# board1.net
KiCad netlist of a schematic drawn in Altium Designer
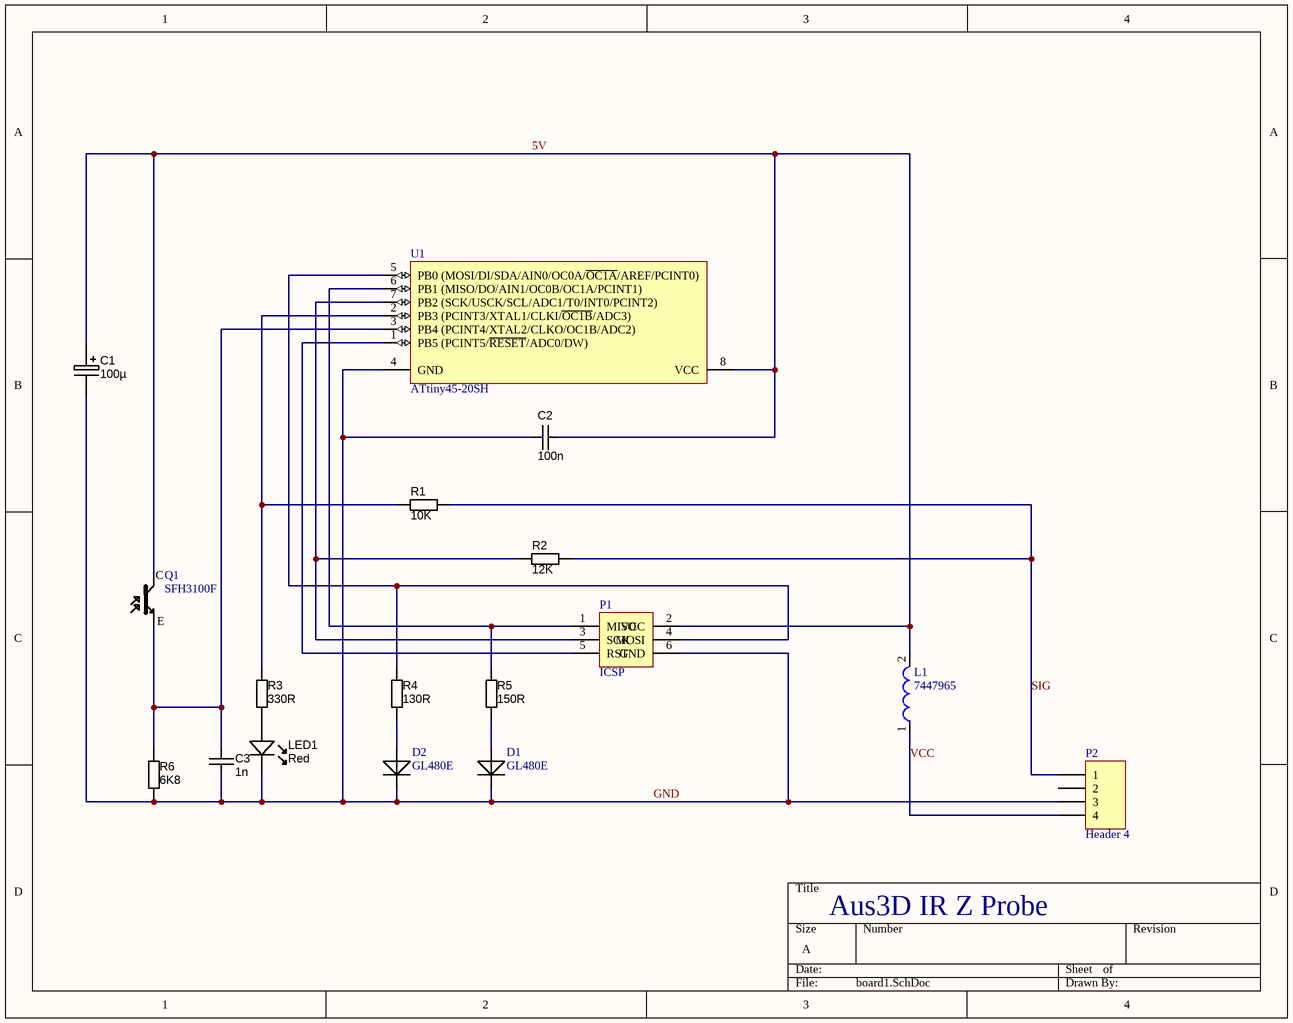
[diagram p0: board1.SchDoc]

(export (version "E")
  (design (tool "Eeschema 10.0.6"))
  (components
    (comp (ref "C1")
      (value "100µ")
      (footprint "6.3-DIA-CAP")
      (description "Capacitor THD Electrolytic 100uF 20% 16V Radial")
      (fields (field (name "TOLERANCE") "±20%") (field (name "MANUFACTURER") "Panasonic - ECG"))
      (libsource (lib "PBL - Capacitors") (part "CAPE_100u_16V_THD"))
    )
    (comp (ref "C2")
      (value "100n")
      (footprint "CAPC1005X55N")
      (description "Capacitor SMD Cer 100nF 10% 16V X5R 0402")
      (fields (field (name "TOLERANCE") "±10%"))
      (libsource (lib "PBL - Capacitors") (part "CAPC_100n_0402_X5R_16V_10%"))
    )
    (comp (ref "C3")
      (value "1n")
      (footprint "CAPC1005X55N")
      (description "Capacitor SMD Cer 1nF 10% 16V X7R 0402")
      (fields (field (name "TOLERANCE") "±10%"))
      (libsource (lib "PBL - Capacitors") (part "CAPC_1n_0402_X7R_16V_10%"))
    )
    (comp (ref "D1")
      (value "GL480E")
      (footprint "LED-2.54spacing")
      (libsource (lib "Schlib1") (part "GL480E"))
    )
    (comp (ref "D2")
      (value "GL480E")
      (footprint "LED-2.54spacing")
      (libsource (lib "Schlib1") (part "GL480E"))
    )
    (comp (ref "L1")
      (value "7447965")
      (footprint "SMD-0603")
      (description "SMD-Multilayer Inductor WE-MI, L = 1.00 µH")
      (libsource (lib "Wuerth Elektronik Filter Inductor") (part "7447965"))
    )
    (comp (ref "LED1")
      (value "Red")
      (footprint "LED-0603-RED")
      (description "LED 0603 SMD Hyper Red 630nm 220mcd 20mA")
      (libsource (lib "PBL - Light Sources") (part "LED_SMD_Red_0603_220mcd"))
    )
    (comp (ref "P1")
      (value "ICSP")
      (footprint "HDR2X3")
      (description "Header, 3-Pin, Dual row")
      (fields (field (name "PUBLISHER") "Altium Limited"))
      (libsource (lib "Miscellaneous Connectors") (part "Header 3X2"))
    )
    (comp (ref "P2")
      (value "Header 4")
      (footprint "JST-4P")
      (description "Header, 4-Pin")
      (fields (field (name "PUBLISHER") "Altium Limited"))
      (libsource (lib "Miscellaneous Connectors") (part "Header 4"))
    )
    (comp (ref "Q1")
      (value "SFH3100F")
      (footprint "SFH3100F-footprint")
      (description "GL480E")
      (libsource (lib "Schlib1") (part "SFH3100F"))
    )
    (comp (ref "R1")
      (value "10K")
      (footprint "RESC1608X55N")
      (description "Resistor SMD chip 2.2k Ohm 0.1W 5% 0603")
      (fields (field (name "TOLERANCE") "±5%") (field (name "Comment") "Thick Film"))
      (libsource (lib "") (part "RES_2K2_0603_5%_1"))
    )
    (comp (ref "R2")
      (value "12K")
      (footprint "RESC1608X55N")
      (description "Resistor SMD chip 2.2k Ohm 0.1W 5% 0603")
      (fields (field (name "TOLERANCE") "±5%") (field (name "Comment") "Thick Film"))
      (libsource (lib "") (part "RES_2K2_0603_5%_1"))
    )
    (comp (ref "R3")
      (value "330R")
      (footprint "RESC1608X55N")
      (description "Resistor SMD chip 330 Ohm 0.1W 5% 0603")
      (fields (field (name "TOLERANCE") "±5%") (field (name "Comment") "Thick Film"))
      (libsource (lib "PBL - Resistors") (part "RES_330R_0603_5%"))
    )
    (comp (ref "R4")
      (value "130R")
      (footprint "RESC1608X55N")
      (description "Resistor SMD chip 2.2k Ohm 0.1W 5% 0603")
      (fields (field (name "TOLERANCE") "±5%") (field (name "Comment") "Thick Film"))
      (libsource (lib "PBL - Resistors") (part "RES_2K2_0603_5%"))
    )
    (comp (ref "R5")
      (value "150R")
      (footprint "RESC1608X55N")
      (description "Resistor SMD chip 2.2k Ohm 0.1W 5% 0603")
      (fields (field (name "TOLERANCE") "±5%") (field (name "Comment") "Thick Film"))
      (libsource (lib "PBL - Resistors") (part "RES_2K2_0603_5%"))
    )
    (comp (ref "R6")
      (value "6K8")
      (footprint "RESC1608X55N")
      (description "Resistor SMD chip 2.2k Ohm 0.1W 5% 0603")
      (fields (field (name "TOLERANCE") "±5%") (field (name "Comment") "Thick Film"))
      (libsource (lib "PBL - Resistors") (part "RES_2K2_0603_5%"))
    )
    (comp (ref "U1")
      (value "ATtiny45-20SH")
      (footprint "8S2_N")
      (libsource (lib "Atmel Microcontroller tinyAVR") (part "ATtiny45-20SH"))
    )
  )
  (nets
    (net (code "1") (name "/5V") (class "Default")
      (node (ref "C1") (pin "1") (pintype "passive"))
      (node (ref "C2") (pin "2") (pintype "passive"))
      (node (ref "L1") (pin "2") (pinfunction "2_2") (pintype "passive"))
      (node (ref "P1") (pin "2") (pinfunction "VCC_2") (pintype "passive"))
      (node (ref "Q1") (pin "1") (pinfunction "1_1") (pintype "passive"))
      (node (ref "U1") (pin "8") (pinfunction "VCC_8") (pintype "power_in"))
    )
    (net (code "2") (name "/GND") (class "Default")
      (node (ref "C1") (pin "2") (pintype "passive"))
      (node (ref "C2") (pin "1") (pintype "passive"))
      (node (ref "C3") (pin "2") (pintype "passive"))
      (node (ref "D1") (pin "1") (pinfunction "1_1") (pintype "passive"))
      (node (ref "D2") (pin "1") (pinfunction "1_1") (pintype "passive"))
      (node (ref "LED1") (pin "K") (pinfunction "K_K") (pintype "passive"))
      (node (ref "P1") (pin "6") (pinfunction "GND_6") (pintype "passive"))
      (node (ref "P2") (pin "3") (pinfunction "3_3") (pintype "passive"))
      (node (ref "R6") (pin "1") (pinfunction "1_1") (pintype "passive"))
      (node (ref "U1") (pin "4") (pinfunction "GND_4") (pintype "power_in"))
    )
    (net (code "3") (name "/SIG") (class "Default")
      (node (ref "P2") (pin "1") (pinfunction "1_1") (pintype "passive"))
      (node (ref "R1") (pin "1") (pinfunction "1_1") (pintype "passive"))
      (node (ref "R2") (pin "1") (pinfunction "1_1") (pintype "passive"))
    )
    (net (code "4") (name "/VCC") (class "Default")
      (node (ref "L1") (pin "1") (pinfunction "1_1") (pintype "passive"))
      (node (ref "P2") (pin "4") (pinfunction "4_4") (pintype "passive"))
    )
    (net (code "5") (name "Net-(D1-Pad2)") (class "Default")
      (node (ref "D1") (pin "2") (pinfunction "2_2") (pintype "passive"))
      (node (ref "R5") (pin "1") (pinfunction "1_1") (pintype "passive"))
    )
    (net (code "6") (name "Net-(D2-Pad2)") (class "Default")
      (node (ref "D2") (pin "2") (pinfunction "2_2") (pintype "passive"))
      (node (ref "R4") (pin "1") (pinfunction "1_1") (pintype "passive"))
    )
    (net (code "7") (name "Net-(LED1-PadA)") (class "Default")
      (node (ref "LED1") (pin "A") (pinfunction "A_A") (pintype "passive"))
      (node (ref "R3") (pin "2") (pinfunction "2_2") (pintype "passive"))
    )
    (net (code "8") (name "Net-(P1-MISO)") (class "Default")
      (node (ref "P1") (pin "1") (pinfunction "MISO_1") (pintype "passive"))
      (node (ref "R5") (pin "2") (pinfunction "2_2") (pintype "passive"))
      (node (ref "U1") (pin "6") (pinfunction "PB1_(MISO/DO/AIN1/OC0B/OC1A/PCINT1)_6") (pintype "bidirectional"))
    )
    (net (code "9") (name "Net-(P1-MOSI)") (class "Default")
      (node (ref "P1") (pin "4") (pinfunction "MOSI_4") (pintype "passive"))
      (node (ref "R4") (pin "2") (pinfunction "2_2") (pintype "passive"))
      (node (ref "U1") (pin "5") (pinfunction "PB0_(MOSI/DI/SDA/AIN0/OC0A/~{OC1A}/AREF/PCINT0)_5") (pintype "bidirectional"))
    )
    (net (code "10") (name "Net-(P1-RST)") (class "Default")
      (node (ref "P1") (pin "5") (pinfunction "RST_5") (pintype "passive"))
      (node (ref "U1") (pin "1") (pinfunction "PB5_(PCINT5/~{RESET}/ADC0/DW)_1") (pintype "bidirectional"))
    )
    (net (code "11") (name "Net-(P1-SCK)") (class "Default")
      (node (ref "P1") (pin "3") (pinfunction "SCK_3") (pintype "passive"))
      (node (ref "R2") (pin "2") (pinfunction "2_2") (pintype "passive"))
      (node (ref "U1") (pin "7") (pinfunction "PB2_(SCK/USCK/SCL/ADC1/T0/INT0/PCINT2)_7") (pintype "bidirectional"))
    )
    (net (code "12") (name "Net-(U1-PB3_(PCINT3{slash}XTAL1{slash}CLKI{slash}~{OC1B}{slash}ADC3))") (class "Default")
      (node (ref "R1") (pin "2") (pinfunction "2_2") (pintype "passive"))
      (node (ref "R3") (pin "1") (pinfunction "1_1") (pintype "passive"))
      (node (ref "U1") (pin "2") (pinfunction "PB3_(PCINT3/XTAL1/CLKI/~{OC1B}/ADC3)_2") (pintype "bidirectional"))
    )
    (net (code "13") (name "Net-(U1-PB4_(PCINT4{slash}XTAL2{slash}CLKO{slash}OC1B{slash}ADC2))") (class "Default")
      (node (ref "C3") (pin "1") (pintype "passive"))
      (node (ref "Q1") (pin "2") (pinfunction "2_2") (pintype "passive"))
      (node (ref "R6") (pin "2") (pinfunction "2_2") (pintype "passive"))
      (node (ref "U1") (pin "3") (pinfunction "PB4_(PCINT4/XTAL2/CLKO/OC1B/ADC2)_3") (pintype "bidirectional"))
    )
    (net (code "14") (name "unconnected-(P2-Pad2)") (class "Default")
      (node (ref "P2") (pin "2") (pinfunction "2_2") (pintype "passive"))
    )
  )
)
